# avoccado-nora-test-jig.net
KiCad netlist of a schematic drawn in EAGLE
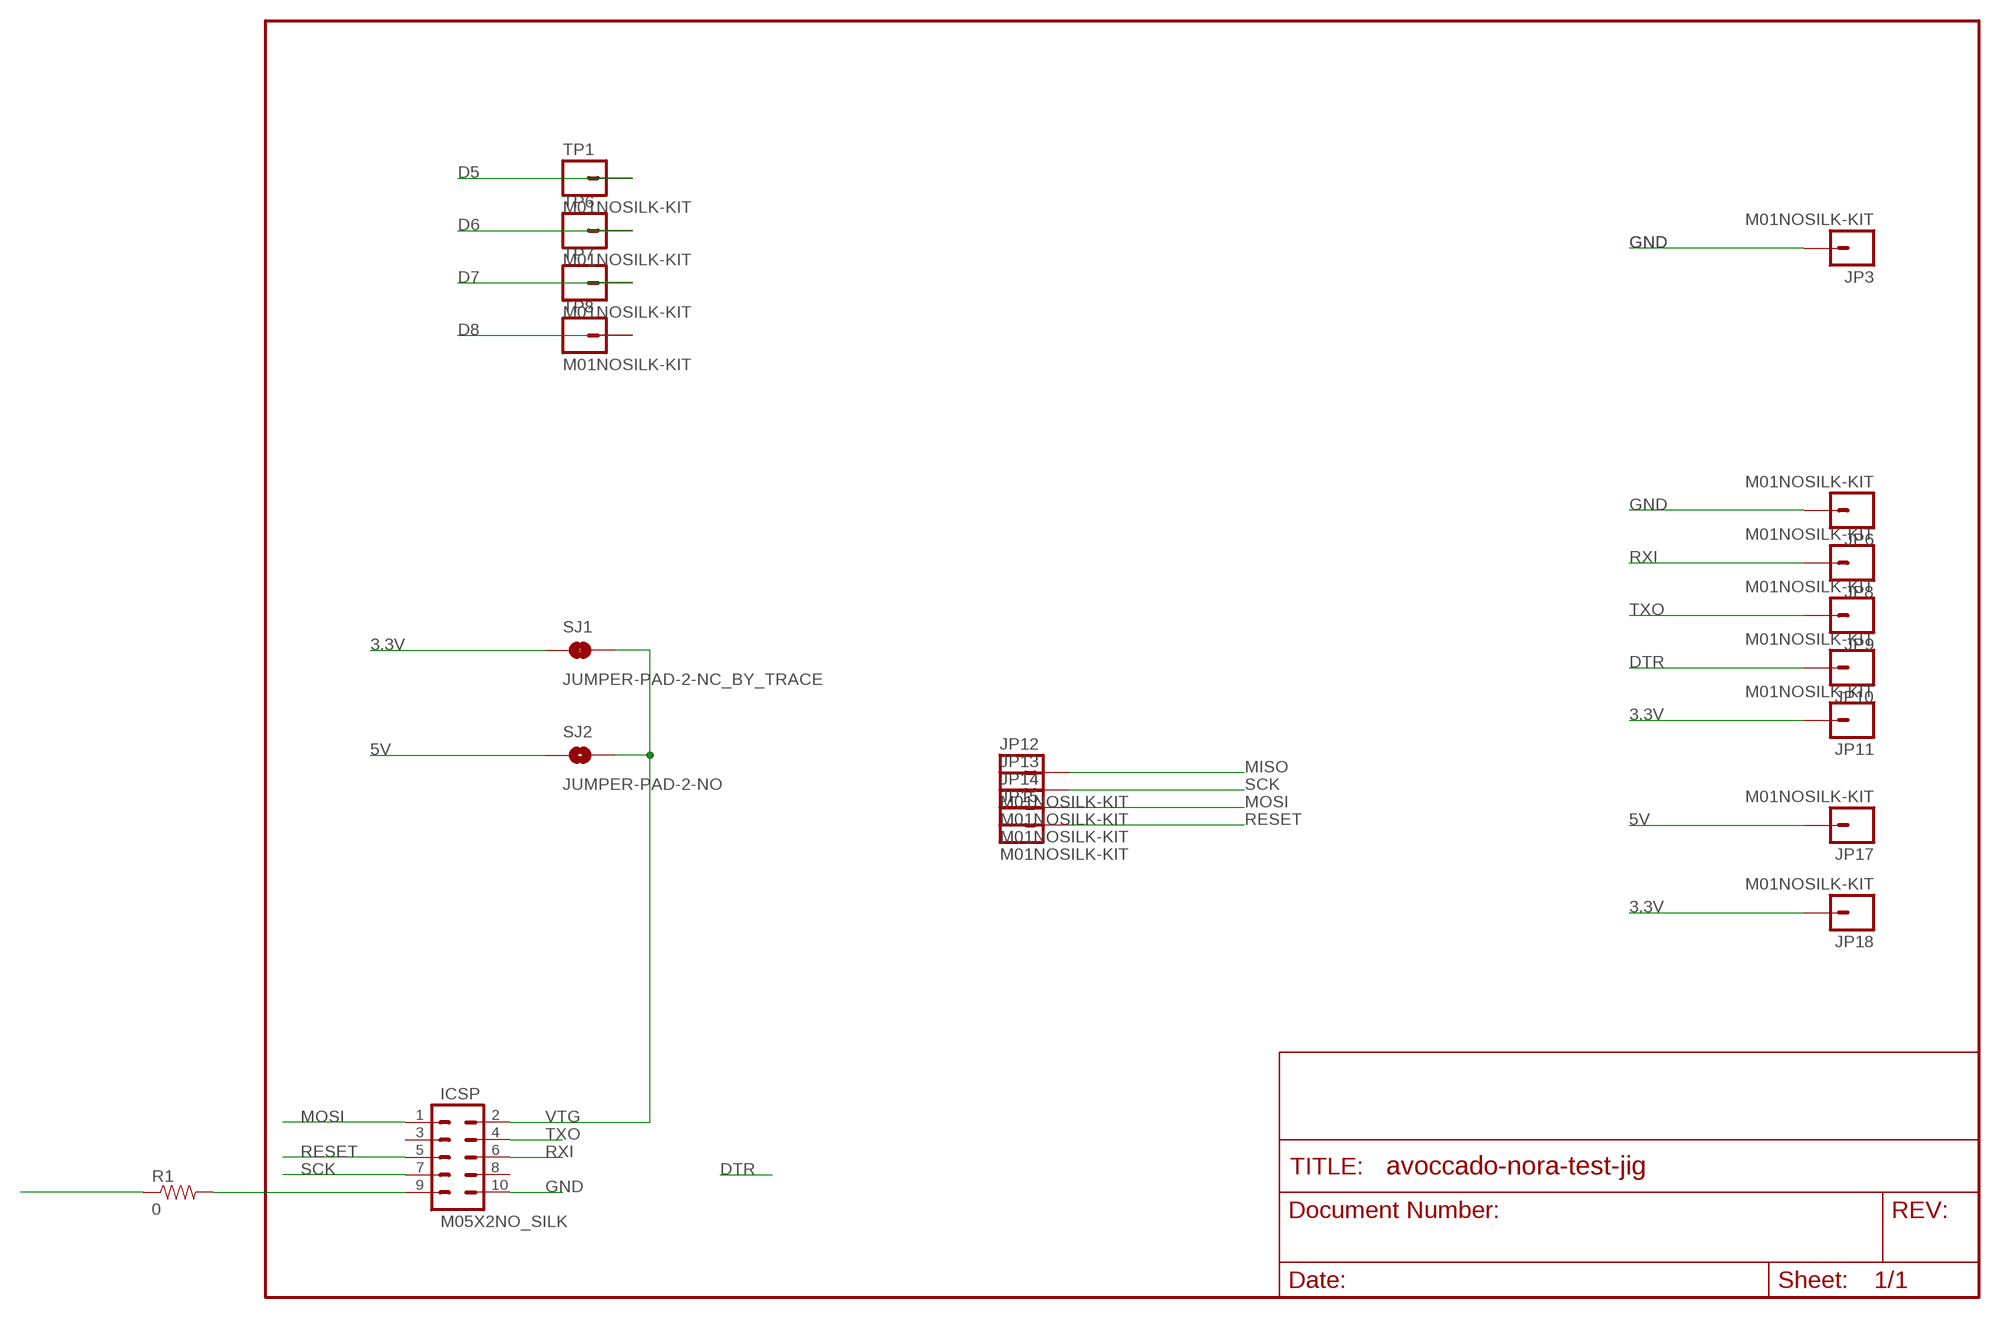
[diagram p0: schematic, sheet 1]

(export (version "E")
  (design (tool "Eeschema 10.0.6"))
  (components
    (comp (ref "ICSP")
      (value "M05X2NO_SILK")
      (footprint "eagle-import:2X5_NOSILK")
      (libsource (lib "eagle-import") (part "M05X2NO_SILK"))
    )
    (comp (ref "JP3")
      (value "M01NOSILK-KIT")
      (footprint "eagle-import:1X01NS-KIT")
      (libsource (lib "eagle-import") (part "M01NOSILK-KIT"))
    )
    (comp (ref "JP6")
      (value "M01NOSILK-KIT")
      (footprint "eagle-import:1X01NS-KIT")
      (libsource (lib "eagle-import") (part "M01NOSILK-KIT"))
    )
    (comp (ref "JP8")
      (value "M01NOSILK-KIT")
      (footprint "eagle-import:1X01NS-KIT")
      (libsource (lib "eagle-import") (part "M01NOSILK-KIT"))
    )
    (comp (ref "JP9")
      (value "M01NOSILK-KIT")
      (footprint "eagle-import:1X01NS-KIT")
      (libsource (lib "eagle-import") (part "M01NOSILK-KIT"))
    )
    (comp (ref "JP10")
      (value "M01NOSILK-KIT")
      (footprint "eagle-import:1X01NS-KIT")
      (libsource (lib "eagle-import") (part "M01NOSILK-KIT"))
    )
    (comp (ref "JP11")
      (value "M01NOSILK-KIT")
      (footprint "eagle-import:1X01NS-KIT")
      (libsource (lib "eagle-import") (part "M01NOSILK-KIT"))
    )
    (comp (ref "JP12")
      (value "M01NOSILK-KIT")
      (footprint "eagle-import:1X01NS-KIT")
      (libsource (lib "eagle-import") (part "M01NOSILK-KIT"))
    )
    (comp (ref "JP13")
      (value "M01NOSILK-KIT")
      (footprint "eagle-import:1X01NS-KIT")
      (libsource (lib "eagle-import") (part "M01NOSILK-KIT"))
    )
    (comp (ref "JP14")
      (value "M01NOSILK-KIT")
      (footprint "eagle-import:1X01NS-KIT")
      (libsource (lib "eagle-import") (part "M01NOSILK-KIT"))
    )
    (comp (ref "JP15")
      (value "M01NOSILK-KIT")
      (footprint "eagle-import:1X01NS-KIT")
      (libsource (lib "eagle-import") (part "M01NOSILK-KIT"))
    )
    (comp (ref "JP17")
      (value "M01NOSILK-KIT")
      (footprint "eagle-import:1X01NS-KIT")
      (libsource (lib "eagle-import") (part "M01NOSILK-KIT"))
    )
    (comp (ref "JP18")
      (value "M01NOSILK-KIT")
      (footprint "eagle-import:1X01NS-KIT")
      (libsource (lib "eagle-import") (part "M01NOSILK-KIT"))
    )
    (comp (ref "R1")
      (value "0")
      (footprint "eagle-import:1206")
      (libsource (lib "eagle-import") (part "RESISTOR1206"))
    )
    (comp (ref "SJ1")
      (value "JUMPER-PAD-2-NC_BY_TRACE")
      (footprint "eagle-import:PAD-JUMPER-2-NC_BY_TRACE_YES_SILK")
      (libsource (lib "eagle-import") (part "JUMPER-PAD-2-NC_BY_TRACE"))
    )
    (comp (ref "SJ2")
      (value "JUMPER-PAD-2-NO")
      (footprint "eagle-import:PAD-JUMPER-2-NO_NO_SILK")
      (libsource (lib "eagle-import") (part "JUMPER-PAD-2-NO"))
    )
    (comp (ref "TP1")
      (value "M01NOSILK-KIT")
      (footprint "eagle-import:1X01NS-KIT")
      (libsource (lib "eagle-import") (part "M01NOSILK-KIT"))
    )
    (comp (ref "TP6")
      (value "M01NOSILK-KIT")
      (footprint "eagle-import:1X01NS-KIT")
      (libsource (lib "eagle-import") (part "M01NOSILK-KIT"))
    )
    (comp (ref "TP7")
      (value "M01NOSILK-KIT")
      (footprint "eagle-import:1X01NS-KIT")
      (libsource (lib "eagle-import") (part "M01NOSILK-KIT"))
    )
    (comp (ref "TP8")
      (value "M01NOSILK-KIT")
      (footprint "eagle-import:1X01NS-KIT")
      (libsource (lib "eagle-import") (part "M01NOSILK-KIT"))
    )
  )
  (nets
    (net (code "1") (name "/3.3V") (class "Default")
      (node (ref "JP11") (pin "1") (pinfunction "1_1") (pintype "passive"))
      (node (ref "JP18") (pin "1") (pinfunction "1_1") (pintype "passive"))
      (node (ref "SJ1") (pin "1") (pinfunction "1_1") (pintype "passive"))
    )
    (net (code "2") (name "/5V") (class "Default")
      (node (ref "JP17") (pin "1") (pinfunction "1_1") (pintype "passive"))
      (node (ref "SJ2") (pin "1") (pinfunction "1_1") (pintype "passive"))
    )
    (net (code "3") (name "/D5") (class "Default")
      (node (ref "TP1") (pin "1") (pinfunction "1_1") (pintype "passive"))
    )
    (net (code "4") (name "/D6") (class "Default")
      (node (ref "TP6") (pin "1") (pinfunction "1_1") (pintype "passive"))
    )
    (net (code "5") (name "/D7") (class "Default")
      (node (ref "TP7") (pin "1") (pinfunction "1_1") (pintype "passive"))
    )
    (net (code "6") (name "/D8") (class "Default")
      (node (ref "TP8") (pin "1") (pinfunction "1_1") (pintype "passive"))
    )
    (net (code "7") (name "/DTR") (class "Default")
      (node (ref "JP10") (pin "1") (pinfunction "1_1") (pintype "passive"))
    )
    (net (code "8") (name "/GND") (class "Default")
      (node (ref "ICSP") (pin "10") (pinfunction "10_10") (pintype "passive"))
      (node (ref "JP3") (pin "1") (pinfunction "1_1") (pintype "passive"))
      (node (ref "JP6") (pin "1") (pinfunction "1_1") (pintype "passive"))
    )
    (net (code "9") (name "/MISO") (class "Default")
      (node (ref "JP12") (pin "1") (pinfunction "1_1") (pintype "passive"))
      (node (ref "R1") (pin "1") (pinfunction "1_1") (pintype "passive"))
    )
    (net (code "10") (name "/MOSI") (class "Default")
      (node (ref "ICSP") (pin "1") (pinfunction "1_1") (pintype "passive"))
      (node (ref "JP14") (pin "1") (pinfunction "1_1") (pintype "passive"))
    )
    (net (code "11") (name "/RESET") (class "Default")
      (node (ref "ICSP") (pin "5") (pinfunction "5_5") (pintype "passive"))
      (node (ref "JP15") (pin "1") (pinfunction "1_1") (pintype "passive"))
    )
    (net (code "12") (name "/RXI") (class "Default")
      (node (ref "ICSP") (pin "6") (pinfunction "6_6") (pintype "passive"))
      (node (ref "JP8") (pin "1") (pinfunction "1_1") (pintype "passive"))
    )
    (net (code "13") (name "/SCK") (class "Default")
      (node (ref "ICSP") (pin "7") (pinfunction "7_7") (pintype "passive"))
      (node (ref "JP13") (pin "1") (pinfunction "1_1") (pintype "passive"))
    )
    (net (code "14") (name "/TXO") (class "Default")
      (node (ref "ICSP") (pin "4") (pinfunction "4_4") (pintype "passive"))
      (node (ref "JP9") (pin "1") (pinfunction "1_1") (pintype "passive"))
    )
    (net (code "15") (name "/VTG") (class "Default")
      (node (ref "ICSP") (pin "2") (pinfunction "2_2") (pintype "passive"))
      (node (ref "SJ1") (pin "2") (pinfunction "2_2") (pintype "passive"))
      (node (ref "SJ2") (pin "2") (pinfunction "2_2") (pintype "passive"))
    )
    (net (code "16") (name "Net-(ICSP-Pad9)") (class "Default")
      (node (ref "ICSP") (pin "9") (pinfunction "9_9") (pintype "passive"))
      (node (ref "R1") (pin "2") (pinfunction "2_2") (pintype "passive"))
    )
    (net (code "17") (name "unconnected-(ICSP-Pad3)") (class "Default")
      (node (ref "ICSP") (pin "3") (pinfunction "3_3") (pintype "passive"))
    )
    (net (code "18") (name "unconnected-(ICSP-Pad8)") (class "Default")
      (node (ref "ICSP") (pin "8") (pinfunction "8_8") (pintype "passive"))
    )
  )
)
